# LMD18200_2_7_5.net
KiCad netlist of a schematic drawn in EAGLE
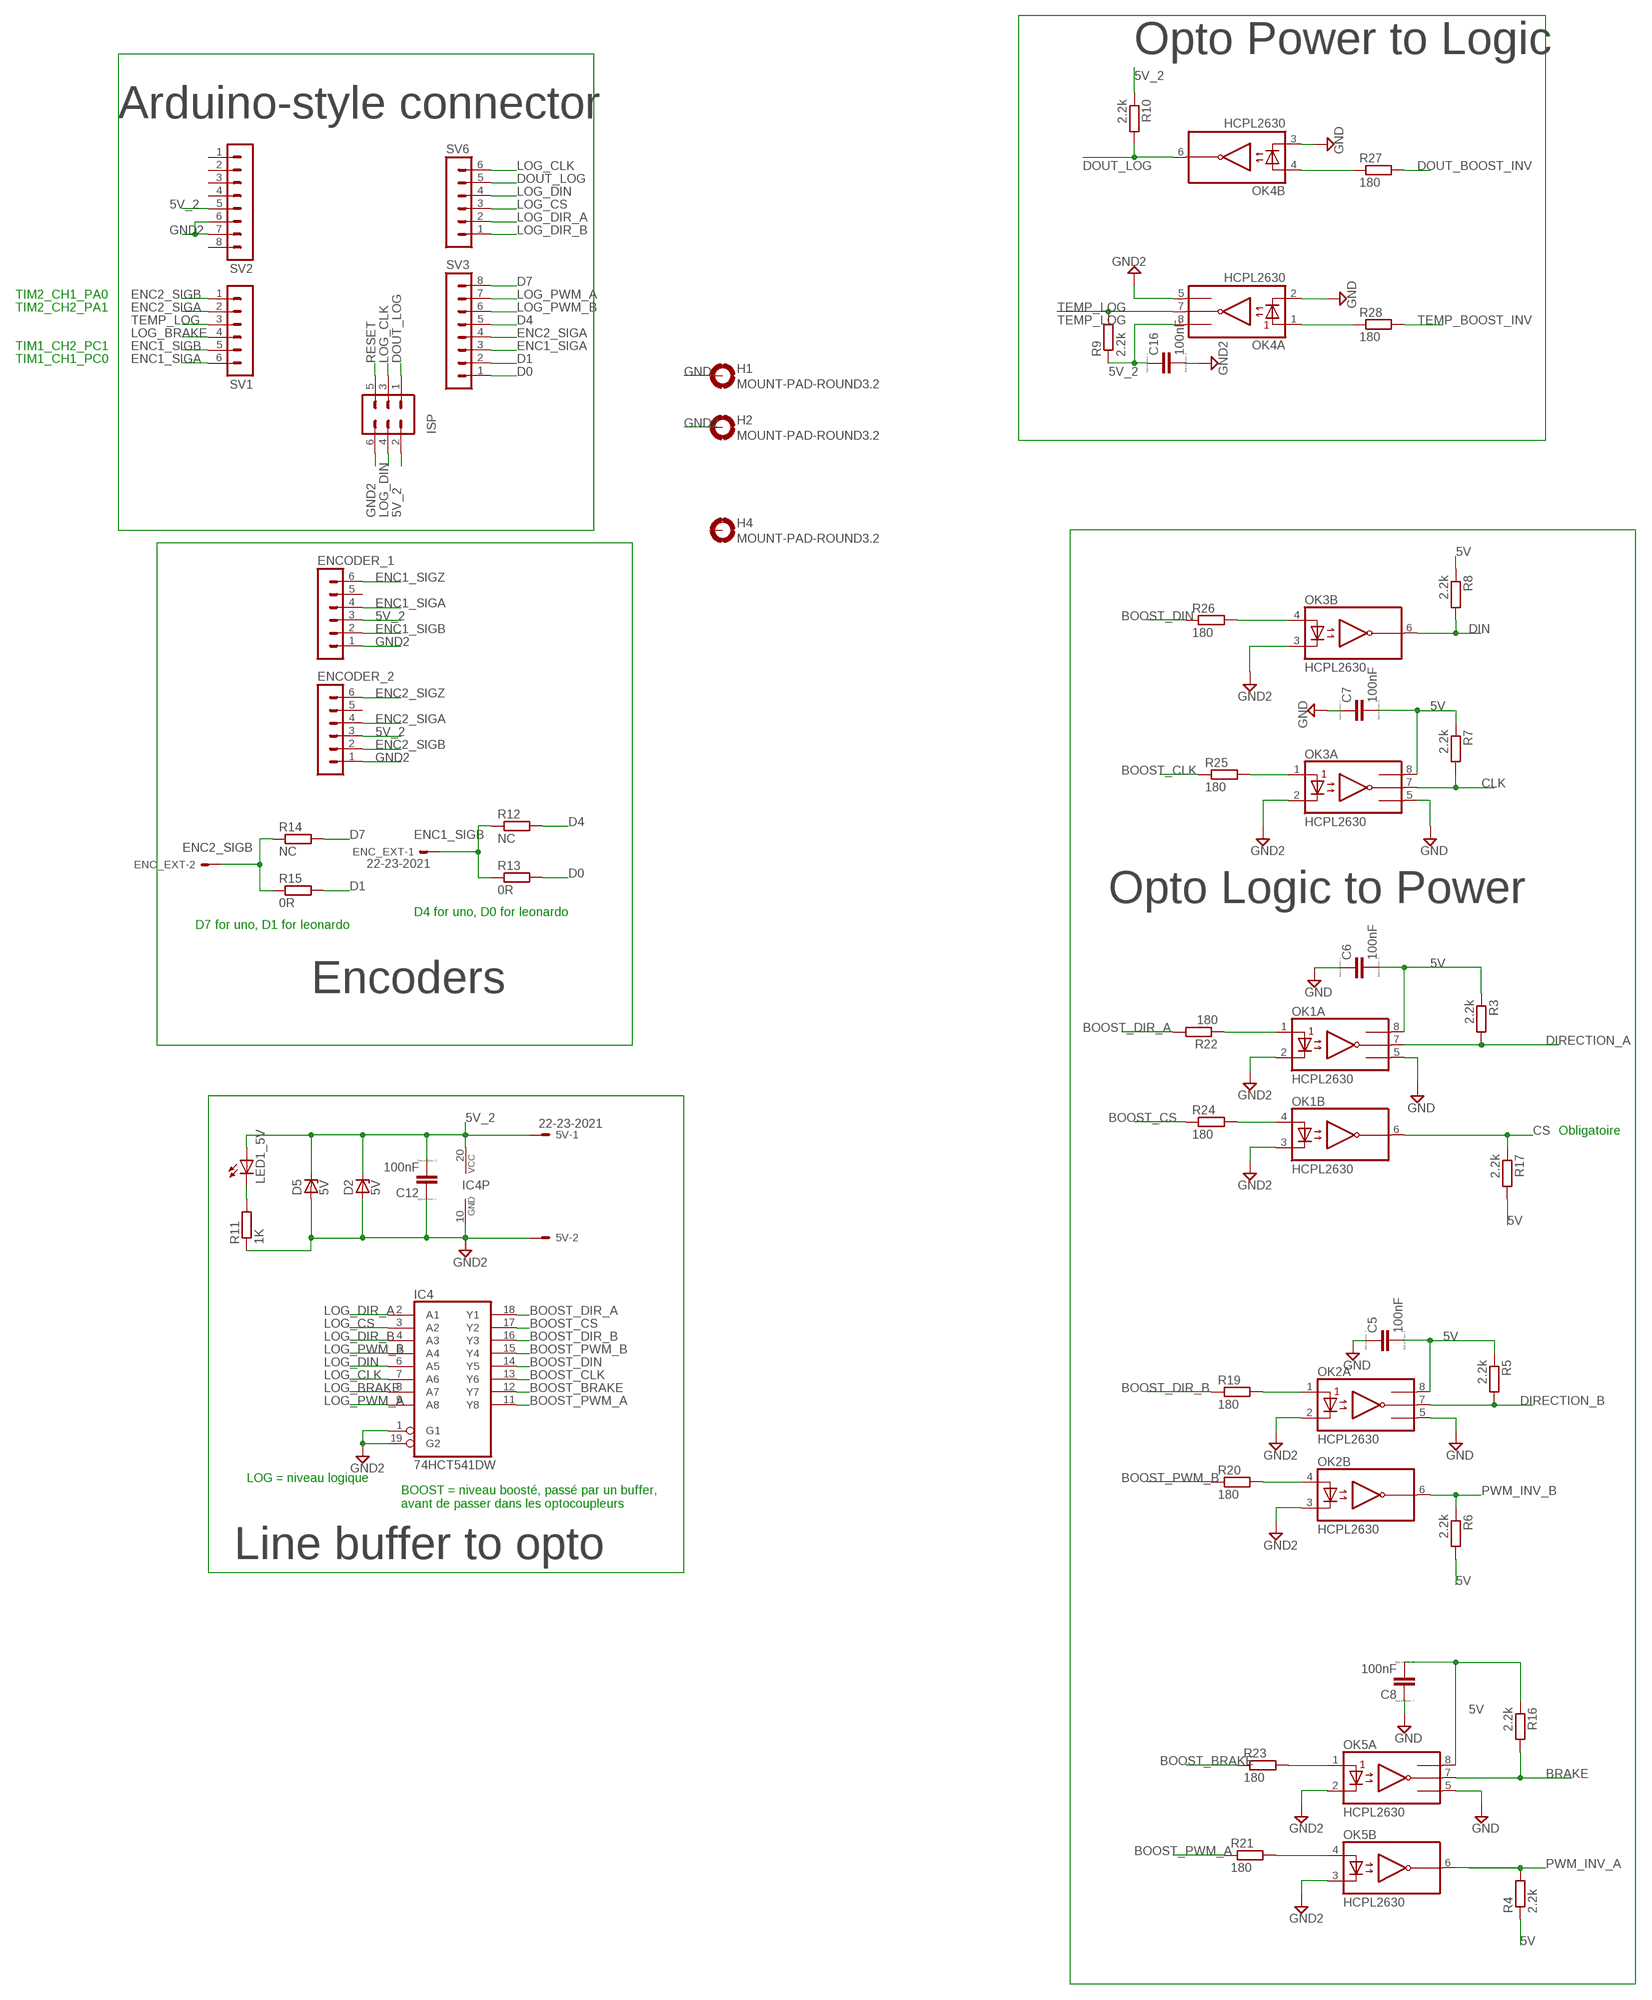
[diagram p0: schematic, sheet 1, part 1 of 2]
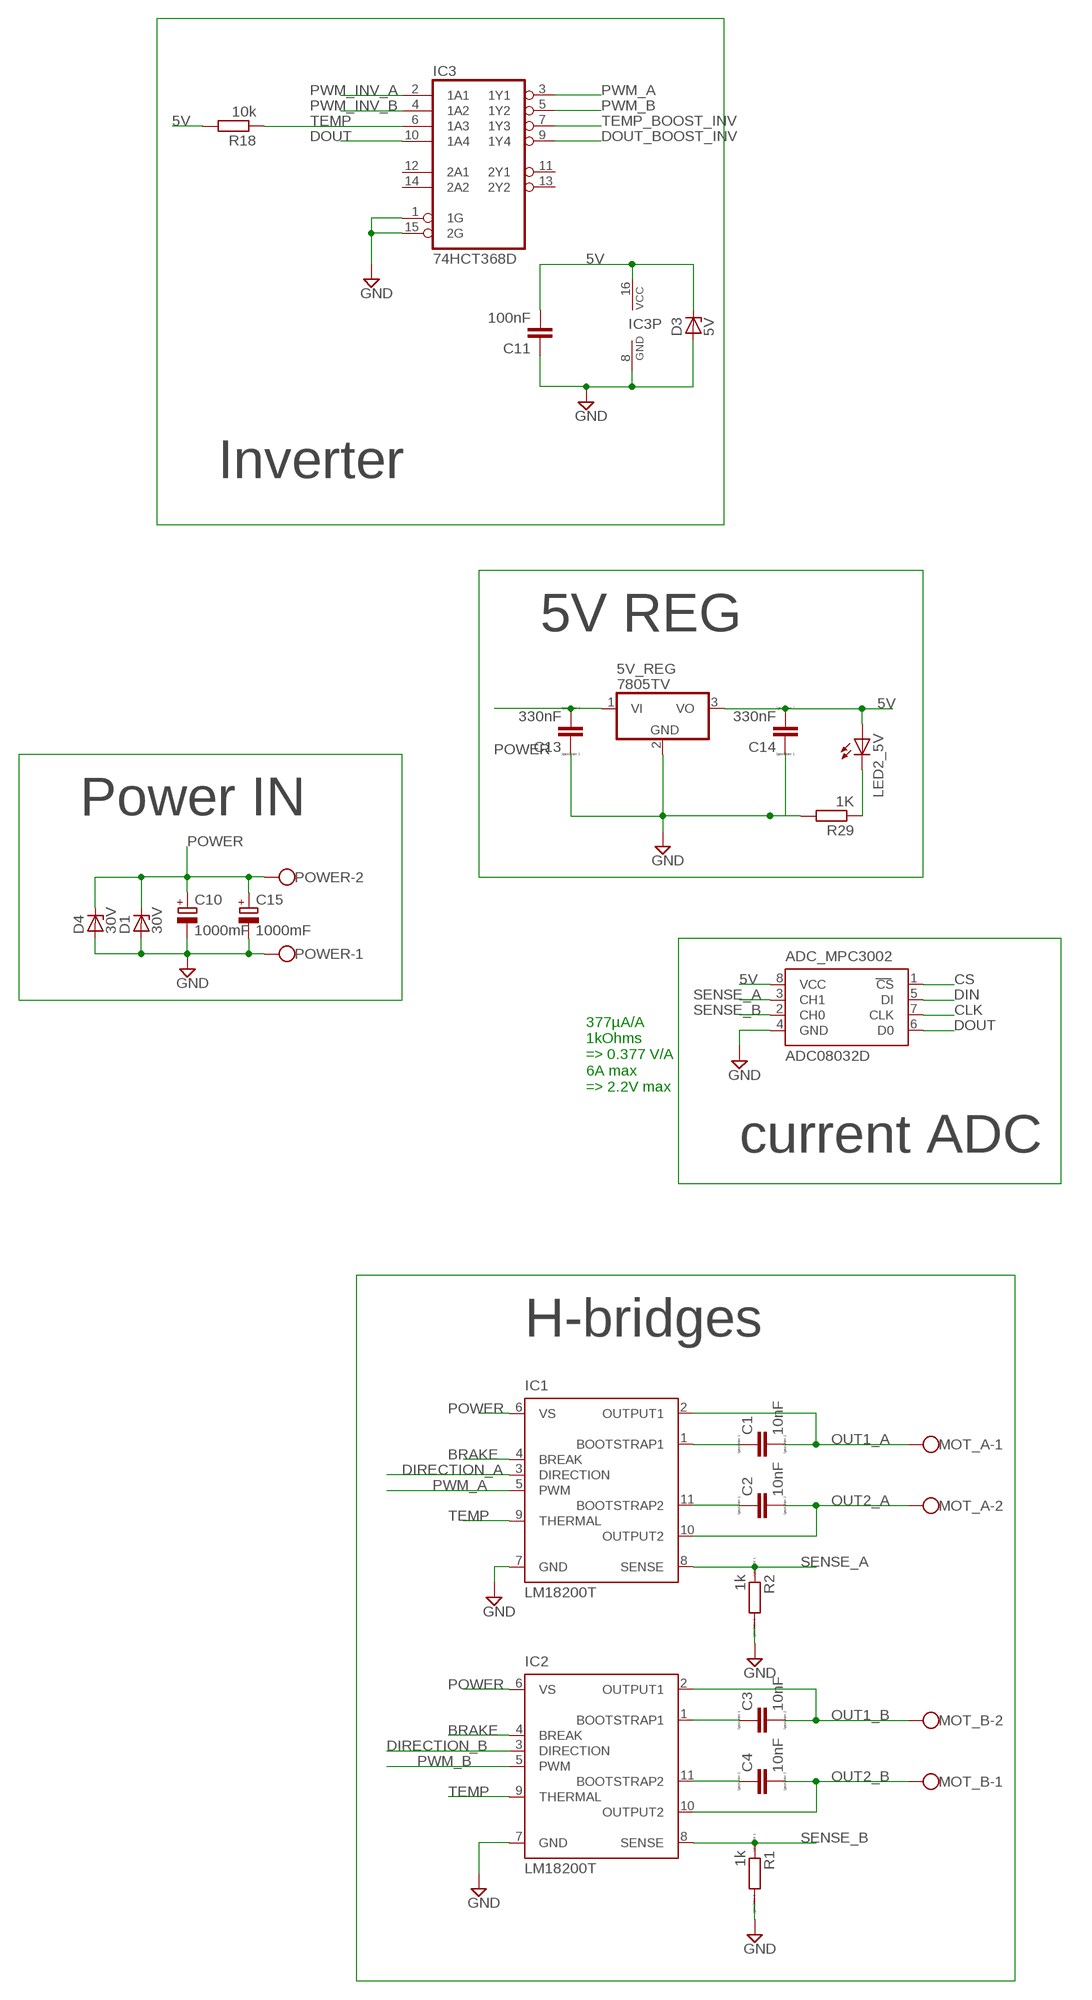
[diagram p1: schematic, sheet 1, part 2 of 2]

(export (version "E")
  (design (tool "Eeschema 10.0.6"))
  (components
    (comp (ref "5V")
      (value "22-23-2021")
      (footprint "eagle-import:22-23-2021")
      (fields (field (name "MF") "MOLEX"))
      (libsource (lib "eagle-import") (part "22-23-2021"))
    )
    (comp (ref "5V_REG")
      (value "7805TV")
      (footprint "eagle-import:TO220V")
      (libsource (lib "eagle-import") (part "78TV05"))
    )
    (comp (ref "ADC_MPC3002")
      (value "ADC08032D")
      (footprint "eagle-import:SO08")
      (libsource (lib "eagle-import") (part "ADC08032D"))
    )
    (comp (ref "C1")
      (value "10nF")
      (footprint "eagle-import:C0603")
      (libsource (lib "eagle-import") (part "CC0603"))
    )
    (comp (ref "C2")
      (value "10nF")
      (footprint "eagle-import:C0603")
      (libsource (lib "eagle-import") (part "CC0603"))
    )
    (comp (ref "C3")
      (value "10nF")
      (footprint "eagle-import:C0603")
      (libsource (lib "eagle-import") (part "CC0603"))
    )
    (comp (ref "C4")
      (value "10nF")
      (footprint "eagle-import:C0603")
      (libsource (lib "eagle-import") (part "CC0603"))
    )
    (comp (ref "C5")
      (value "100nF")
      (footprint "eagle-import:C0603")
      (libsource (lib "eagle-import") (part "CC0603"))
    )
    (comp (ref "C6")
      (value "100nF")
      (footprint "eagle-import:C0603")
      (libsource (lib "eagle-import") (part "CC0603"))
    )
    (comp (ref "C7")
      (value "100nF")
      (footprint "eagle-import:C0603")
      (libsource (lib "eagle-import") (part "CC0603"))
    )
    (comp (ref "C8")
      (value "100nF")
      (footprint "eagle-import:C0603")
      (libsource (lib "eagle-import") (part "CC0603"))
    )
    (comp (ref "C10")
      (value "1000mF")
      (footprint "eagle-import:E5-13")
      (libsource (lib "eagle-import") (part "CPOL-EUE5-13"))
    )
    (comp (ref "C11")
      (value "100nF")
      (footprint "eagle-import:C0805")
      (libsource (lib "eagle-import") (part "C-EUC0805"))
    )
    (comp (ref "C12")
      (value "100nF")
      (footprint "eagle-import:C0603")
      (libsource (lib "eagle-import") (part "CC0603"))
    )
    (comp (ref "C13")
      (value "330nF")
      (footprint "eagle-import:C0603")
      (libsource (lib "eagle-import") (part "CC0603"))
    )
    (comp (ref "C14")
      (value "330nF")
      (footprint "eagle-import:C0603")
      (libsource (lib "eagle-import") (part "CC0603"))
    )
    (comp (ref "C15")
      (value "1000mF")
      (footprint "eagle-import:E5-13")
      (libsource (lib "eagle-import") (part "CPOL-EUE5-13"))
    )
    (comp (ref "C16")
      (value "100nF")
      (footprint "eagle-import:C0603")
      (libsource (lib "eagle-import") (part "CC0603"))
    )
    (comp (ref "D1")
      (value "30V")
      (footprint "eagle-import:SOD80C")
      (libsource (lib "eagle-import") (part "ZENER-DIODESOD80C"))
    )
    (comp (ref "D2")
      (value "5V")
      (footprint "eagle-import:SOD80C")
      (libsource (lib "eagle-import") (part "ZENER-DIODESOD80C"))
    )
    (comp (ref "D3")
      (value "5V")
      (footprint "eagle-import:DO34Z7")
      (libsource (lib "eagle-import") (part "ZENER-DIODEDO34-7"))
    )
    (comp (ref "D4")
      (value "30V")
      (footprint "eagle-import:DO34Z7")
      (libsource (lib "eagle-import") (part "ZENER-DIODEDO34-7"))
    )
    (comp (ref "D5")
      (value "5V")
      (footprint "eagle-import:DO34Z7")
      (libsource (lib "eagle-import") (part "ZENER-DIODEDO34-7"))
    )
    (comp (ref "ENCODER_1")
      (value "MA06-1")
      (footprint "eagle-import:MA06-1")
      (libsource (lib "eagle-import") (part "MA06-1"))
    )
    (comp (ref "ENCODER_2")
      (value "MA06-1")
      (footprint "eagle-import:MA06-1")
      (libsource (lib "eagle-import") (part "MA06-1"))
    )
    (comp (ref "ENC_EXT")
      (value "22-23-2021")
      (footprint "eagle-import:22-23-2021")
      (fields (field (name "MF") "MOLEX"))
      (libsource (lib "eagle-import") (part "22-23-2021"))
    )
    (comp (ref "H1")
      (value "MOUNT-PAD-ROUND3.2")
      (footprint "eagle-import:3,2-PAD")
      (libsource (lib "eagle-import") (part "MOUNT-PAD-ROUND3.2"))
    )
    (comp (ref "H2")
      (value "MOUNT-PAD-ROUND3.2")
      (footprint "eagle-import:3,2-PAD")
      (libsource (lib "eagle-import") (part "MOUNT-PAD-ROUND3.2"))
    )
    (comp (ref "H4")
      (value "MOUNT-PAD-ROUND3.2")
      (footprint "eagle-import:3,2-PAD")
      (libsource (lib "eagle-import") (part "MOUNT-PAD-ROUND3.2"))
    )
    (comp (ref "IC1")
      (value "LM18200T")
      (footprint "eagle-import:TO-220-11")
      (libsource (lib "eagle-import") (part "LM18200T"))
    )
    (comp (ref "IC2")
      (value "LM18200T")
      (footprint "eagle-import:TO-220-11")
      (libsource (lib "eagle-import") (part "LM18200T"))
    )
    (comp (ref "IC3")
      (value "74HCT368D")
      (footprint "eagle-import:SO16")
      (libsource (lib "eagle-import") (part "74368DHCT"))
    )
    (comp (ref "IC4")
      (value "74HCT541DW")
      (footprint "eagle-import:SO20W")
      (libsource (lib "eagle-import") (part "74541DWHCT"))
    )
    (comp (ref "ISP")
      (value "MA03-2")
      (footprint "eagle-import:MA03-2")
      (libsource (lib "eagle-import") (part "MA03-2"))
    )
    (comp (ref "LED1_5V")
      (value "LEDSML0805")
      (footprint "eagle-import:SML0805")
      (libsource (lib "eagle-import") (part "LEDSML0805"))
    )
    (comp (ref "LED2_5V")
      (value "LEDSML0805")
      (footprint "eagle-import:SML0805")
      (libsource (lib "eagle-import") (part "LEDSML0805"))
    )
    (comp (ref "MOT_A")
      (value "W237-102")
      (footprint "eagle-import:W237-102")
      (fields (field (name "MPN") "237-102"))
      (libsource (lib "eagle-import") (part "W237-102"))
    )
    (comp (ref "MOT_B")
      (value "W237-102")
      (footprint "eagle-import:W237-102")
      (fields (field (name "MPN") "237-102"))
      (libsource (lib "eagle-import") (part "W237-102"))
    )
    (comp (ref "OK1")
      (value "HCPL2630")
      (footprint "eagle-import:DIL08")
      (fields (field (name "MF") "AGILENT TECHNOLOGIES") (field (name "MPN") "HCPL-2630-000E"))
      (libsource (lib "eagle-import") (part "HCPL2630"))
    )
    (comp (ref "OK2")
      (value "HCPL2630")
      (footprint "eagle-import:DIL08")
      (fields (field (name "MF") "AGILENT TECHNOLOGIES") (field (name "MPN") "HCPL-2630-000E"))
      (libsource (lib "eagle-import") (part "HCPL2630"))
    )
    (comp (ref "OK3")
      (value "HCPL2630")
      (footprint "eagle-import:DIL08")
      (fields (field (name "MF") "AGILENT TECHNOLOGIES") (field (name "MPN") "HCPL-2630-000E"))
      (libsource (lib "eagle-import") (part "HCPL2630"))
    )
    (comp (ref "OK4")
      (value "HCPL2630")
      (footprint "eagle-import:DIL08")
      (fields (field (name "MF") "AGILENT TECHNOLOGIES") (field (name "MPN") "HCPL-2630-000E"))
      (libsource (lib "eagle-import") (part "HCPL2630"))
    )
    (comp (ref "OK5")
      (value "HCPL2630")
      (footprint "eagle-import:DIL08")
      (fields (field (name "MF") "AGILENT TECHNOLOGIES") (field (name "MPN") "HCPL-2630-000E"))
      (libsource (lib "eagle-import") (part "HCPL2630"))
    )
    (comp (ref "POWER")
      (value "W237-102")
      (footprint "eagle-import:W237-102")
      (fields (field (name "MPN") "237-102"))
      (libsource (lib "eagle-import") (part "W237-102"))
    )
    (comp (ref "R1")
      (value "1k")
      (footprint "eagle-import:R0603")
      (libsource (lib "eagle-import") (part "RR0603"))
    )
    (comp (ref "R2")
      (value "1k")
      (footprint "eagle-import:R0603")
      (libsource (lib "eagle-import") (part "RR0603"))
    )
    (comp (ref "R3")
      (value "2.2k")
      (footprint "eagle-import:R0603")
      (libsource (lib "eagle-import") (part "R-EU_R0603"))
    )
    (comp (ref "R4")
      (value "2.2k")
      (footprint "eagle-import:R0603")
      (libsource (lib "eagle-import") (part "R-EU_R0603"))
    )
    (comp (ref "R5")
      (value "2.2k")
      (footprint "eagle-import:R0603")
      (libsource (lib "eagle-import") (part "R-EU_R0603"))
    )
    (comp (ref "R6")
      (value "2.2k")
      (footprint "eagle-import:R0603")
      (libsource (lib "eagle-import") (part "R-EU_R0603"))
    )
    (comp (ref "R7")
      (value "2.2k")
      (footprint "eagle-import:R0603")
      (libsource (lib "eagle-import") (part "R-EU_R0603"))
    )
    (comp (ref "R8")
      (value "2.2k")
      (footprint "eagle-import:R0603")
      (libsource (lib "eagle-import") (part "R-EU_R0603"))
    )
    (comp (ref "R9")
      (value "2.2k")
      (footprint "eagle-import:R0603")
      (libsource (lib "eagle-import") (part "R-EU_R0603"))
    )
    (comp (ref "R10")
      (value "2.2k")
      (footprint "eagle-import:R0603")
      (libsource (lib "eagle-import") (part "R-EU_R0603"))
    )
    (comp (ref "R11")
      (value "1K")
      (footprint "eagle-import:R0603")
      (libsource (lib "eagle-import") (part "R-EU_R0603"))
    )
    (comp (ref "R12")
      (value "NC")
      (footprint "eagle-import:R0603")
      (libsource (lib "eagle-import") (part "R-EU_R0603"))
    )
    (comp (ref "R13")
      (value "0R")
      (footprint "eagle-import:R0603")
      (libsource (lib "eagle-import") (part "R-EU_R0603"))
    )
    (comp (ref "R14")
      (value "NC")
      (footprint "eagle-import:R0603")
      (libsource (lib "eagle-import") (part "R-EU_R0603"))
    )
    (comp (ref "R15")
      (value "0R")
      (footprint "eagle-import:R0603")
      (libsource (lib "eagle-import") (part "R-EU_R0603"))
    )
    (comp (ref "R16")
      (value "2.2k")
      (footprint "eagle-import:R0603")
      (libsource (lib "eagle-import") (part "R-EU_R0603"))
    )
    (comp (ref "R17")
      (value "2.2k")
      (footprint "eagle-import:R0603")
      (libsource (lib "eagle-import") (part "R-EU_R0603"))
    )
    (comp (ref "R18")
      (value "10k")
      (footprint "eagle-import:R0603")
      (libsource (lib "eagle-import") (part "R-EU_R0603"))
    )
    (comp (ref "R19")
      (value "180")
      (footprint "eagle-import:R0603")
      (libsource (lib "eagle-import") (part "R-EU_R0603"))
    )
    (comp (ref "R20")
      (value "180")
      (footprint "eagle-import:R0603")
      (libsource (lib "eagle-import") (part "R-EU_R0603"))
    )
    (comp (ref "R21")
      (value "180")
      (footprint "eagle-import:R0603")
      (libsource (lib "eagle-import") (part "R-EU_R0603"))
    )
    (comp (ref "R22")
      (value "180")
      (footprint "eagle-import:R0603")
      (libsource (lib "eagle-import") (part "R-EU_R0603"))
    )
    (comp (ref "R23")
      (value "180")
      (footprint "eagle-import:R0603")
      (libsource (lib "eagle-import") (part "R-EU_R0603"))
    )
    (comp (ref "R24")
      (value "180")
      (footprint "eagle-import:R0603")
      (libsource (lib "eagle-import") (part "R-EU_R0603"))
    )
    (comp (ref "R25")
      (value "180")
      (footprint "eagle-import:R0603")
      (libsource (lib "eagle-import") (part "R-EU_R0603"))
    )
    (comp (ref "R26")
      (value "180")
      (footprint "eagle-import:R0603")
      (libsource (lib "eagle-import") (part "R-EU_R0603"))
    )
    (comp (ref "R27")
      (value "180")
      (footprint "eagle-import:R0603")
      (libsource (lib "eagle-import") (part "R-EU_R0603"))
    )
    (comp (ref "R28")
      (value "180")
      (footprint "eagle-import:R0603")
      (libsource (lib "eagle-import") (part "R-EU_R0603"))
    )
    (comp (ref "R29")
      (value "1K")
      (footprint "eagle-import:R0603")
      (libsource (lib "eagle-import") (part "R-EU_R0603"))
    )
    (comp (ref "SV1")
      (value "MA06-1")
      (footprint "eagle-import:MA06-1")
      (libsource (lib "eagle-import") (part "MA06-1"))
    )
    (comp (ref "SV2")
      (value "MA08-1")
      (footprint "eagle-import:MA08-1")
      (libsource (lib "eagle-import") (part "MA08-1"))
    )
    (comp (ref "SV3")
      (value "MA08-1")
      (footprint "eagle-import:MA08-1")
      (libsource (lib "eagle-import") (part "MA08-1"))
    )
    (comp (ref "SV6")
      (value "MA06-1")
      (footprint "eagle-import:MA06-1")
      (libsource (lib "eagle-import") (part "MA06-1"))
    )
  )
  (nets
    (net (code "1") (name "/5V") (class "Default")
      (node (ref "5V_REG") (pin "3") (pinfunction "VO_3") (pintype "passive"))
      (node (ref "ADC_MPC3002") (pin "8") (pinfunction "VCC_8") (pintype "power_in"))
      (node (ref "C11") (pin "2") (pinfunction "2_2") (pintype "passive"))
      (node (ref "C14") (pin "2") (pinfunction "2_2") (pintype "passive"))
      (node (ref "C5") (pin "2") (pinfunction "2_2") (pintype "passive"))
      (node (ref "C6") (pin "2") (pinfunction "2_2") (pintype "passive"))
      (node (ref "C7") (pin "2") (pinfunction "2_2") (pintype "passive"))
      (node (ref "C8") (pin "2") (pinfunction "2_2") (pintype "passive"))
      (node (ref "D3") (pin "C") (pinfunction "C_C") (pintype "passive"))
      (node (ref "IC3") (pin "16") (pinfunction "VCC_16") (pintype "power_in"))
      (node (ref "LED2_5V") (pin "A") (pinfunction "A_A") (pintype "passive"))
      (node (ref "OK1") (pin "8") (pinfunction "VCC_8") (pintype "passive"))
      (node (ref "OK2") (pin "8") (pinfunction "VCC_8") (pintype "passive"))
      (node (ref "OK3") (pin "8") (pinfunction "VCC_8") (pintype "passive"))
      (node (ref "OK5") (pin "8") (pinfunction "VCC_8") (pintype "passive"))
      (node (ref "R16") (pin "1") (pinfunction "1_1") (pintype "passive"))
      (node (ref "R17") (pin "2") (pinfunction "2_2") (pintype "passive"))
      (node (ref "R18") (pin "2") (pinfunction "2_2") (pintype "passive"))
      (node (ref "R3") (pin "1") (pinfunction "1_1") (pintype "passive"))
      (node (ref "R4") (pin "1") (pinfunction "1_1") (pintype "passive"))
      (node (ref "R5") (pin "1") (pinfunction "1_1") (pintype "passive"))
      (node (ref "R6") (pin "2") (pinfunction "2_2") (pintype "passive"))
      (node (ref "R7") (pin "1") (pinfunction "1_1") (pintype "passive"))
      (node (ref "R8") (pin "1") (pinfunction "1_1") (pintype "passive"))
    )
    (net (code "2") (name "/5V_2") (class "Default")
      (node (ref "5V") (pin "1") (pinfunction "S_1") (pintype "passive"))
      (node (ref "C12") (pin "2") (pinfunction "2_2") (pintype "passive"))
      (node (ref "C16") (pin "1") (pinfunction "1_1") (pintype "passive"))
      (node (ref "D2") (pin "C") (pinfunction "C_C") (pintype "passive"))
      (node (ref "D5") (pin "C") (pinfunction "C_C") (pintype "passive"))
      (node (ref "ENCODER_1") (pin "3") (pinfunction "3_3") (pintype "passive"))
      (node (ref "ENCODER_2") (pin "3") (pinfunction "3_3") (pintype "passive"))
      (node (ref "IC4") (pin "20") (pinfunction "VCC_20") (pintype "power_in"))
      (node (ref "ISP") (pin "2") (pinfunction "2_2") (pintype "passive"))
      (node (ref "LED1_5V") (pin "A") (pinfunction "A_A") (pintype "passive"))
      (node (ref "OK4") (pin "8") (pinfunction "VCC_8") (pintype "passive"))
      (node (ref "R10") (pin "1") (pinfunction "1_1") (pintype "passive"))
      (node (ref "R9") (pin "1") (pinfunction "1_1") (pintype "passive"))
      (node (ref "SV2") (pin "5") (pinfunction "5_5") (pintype "passive"))
    )
    (net (code "3") (name "/BOOST_BRAKE") (class "Default")
      (node (ref "IC4") (pin "12") (pinfunction "Y7_12") (pintype "tri_state"))
      (node (ref "R23") (pin "1") (pinfunction "1_1") (pintype "passive"))
    )
    (net (code "4") (name "/BOOST_CLK") (class "Default")
      (node (ref "IC4") (pin "13") (pinfunction "Y6_13") (pintype "tri_state"))
      (node (ref "R25") (pin "1") (pinfunction "1_1") (pintype "passive"))
    )
    (net (code "5") (name "/BOOST_CS") (class "Default")
      (node (ref "IC4") (pin "17") (pinfunction "Y2_17") (pintype "tri_state"))
      (node (ref "R24") (pin "1") (pinfunction "1_1") (pintype "passive"))
    )
    (net (code "6") (name "/BOOST_DIN") (class "Default")
      (node (ref "IC4") (pin "14") (pinfunction "Y5_14") (pintype "tri_state"))
      (node (ref "R26") (pin "1") (pinfunction "1_1") (pintype "passive"))
    )
    (net (code "7") (name "/BOOST_DIR_A") (class "Default")
      (node (ref "IC4") (pin "18") (pinfunction "Y1_18") (pintype "tri_state"))
      (node (ref "R22") (pin "2") (pinfunction "2_2") (pintype "passive"))
    )
    (net (code "8") (name "/BOOST_DIR_B") (class "Default")
      (node (ref "IC4") (pin "16") (pinfunction "Y3_16") (pintype "tri_state"))
      (node (ref "R19") (pin "1") (pinfunction "1_1") (pintype "passive"))
    )
    (net (code "9") (name "/BOOST_PWM_A") (class "Default")
      (node (ref "IC4") (pin "11") (pinfunction "Y8_11") (pintype "tri_state"))
      (node (ref "R21") (pin "1") (pinfunction "1_1") (pintype "passive"))
    )
    (net (code "10") (name "/BOOST_PWM_B") (class "Default")
      (node (ref "IC4") (pin "15") (pinfunction "Y4_15") (pintype "tri_state"))
      (node (ref "R20") (pin "1") (pinfunction "1_1") (pintype "passive"))
    )
    (net (code "11") (name "/BRAKE") (class "Default")
      (node (ref "IC1") (pin "4") (pinfunction "BREAK_4") (pintype "input"))
      (node (ref "IC2") (pin "4") (pinfunction "BREAK_4") (pintype "input"))
      (node (ref "OK5") (pin "7") (pinfunction "VO1_7") (pintype "passive"))
      (node (ref "R16") (pin "2") (pinfunction "2_2") (pintype "passive"))
    )
    (net (code "12") (name "/CLK") (class "Default")
      (node (ref "ADC_MPC3002") (pin "7") (pinfunction "CLK_7") (pintype "input"))
      (node (ref "OK3") (pin "7") (pinfunction "VO1_7") (pintype "passive"))
      (node (ref "R7") (pin "2") (pinfunction "2_2") (pintype "passive"))
    )
    (net (code "13") (name "/CS") (class "Default")
      (node (ref "ADC_MPC3002") (pin "1") (pinfunction "CS_1") (pintype "input"))
      (node (ref "OK1") (pin "6") (pinfunction "VO2_6") (pintype "passive"))
      (node (ref "R17") (pin "1") (pinfunction "1_1") (pintype "passive"))
    )
    (net (code "14") (name "/D0") (class "Default")
      (node (ref "R13") (pin "2") (pinfunction "2_2") (pintype "passive"))
      (node (ref "SV3") (pin "1") (pinfunction "1_1") (pintype "passive"))
    )
    (net (code "15") (name "/D1") (class "Default")
      (node (ref "R15") (pin "2") (pinfunction "2_2") (pintype "passive"))
      (node (ref "SV3") (pin "2") (pinfunction "2_2") (pintype "passive"))
    )
    (net (code "16") (name "/D4") (class "Default")
      (node (ref "R12") (pin "2") (pinfunction "2_2") (pintype "passive"))
      (node (ref "SV3") (pin "5") (pinfunction "5_5") (pintype "passive"))
    )
    (net (code "17") (name "/D7") (class "Default")
      (node (ref "R14") (pin "2") (pinfunction "2_2") (pintype "passive"))
      (node (ref "SV3") (pin "8") (pinfunction "8_8") (pintype "passive"))
    )
    (net (code "18") (name "/DIN") (class "Default")
      (node (ref "ADC_MPC3002") (pin "5") (pinfunction "DI_5") (pintype "input"))
      (node (ref "OK3") (pin "6") (pinfunction "VO2_6") (pintype "passive"))
      (node (ref "R8") (pin "2") (pinfunction "2_2") (pintype "passive"))
    )
    (net (code "19") (name "/DIRECTION_A") (class "Default")
      (node (ref "IC1") (pin "3") (pinfunction "DIRECTION_3") (pintype "input"))
      (node (ref "OK1") (pin "7") (pinfunction "VO1_7") (pintype "passive"))
      (node (ref "R3") (pin "2") (pinfunction "2_2") (pintype "passive"))
    )
    (net (code "20") (name "/DIRECTION_B") (class "Default")
      (node (ref "IC2") (pin "3") (pinfunction "DIRECTION_3") (pintype "input"))
      (node (ref "OK2") (pin "7") (pinfunction "VO1_7") (pintype "passive"))
      (node (ref "R5") (pin "2") (pinfunction "2_2") (pintype "passive"))
    )
    (net (code "21") (name "/DOUT") (class "Default")
      (node (ref "ADC_MPC3002") (pin "6") (pinfunction "D0_6") (pintype "tri_state"))
      (node (ref "IC3") (pin "10") (pinfunction "1A4_10") (pintype "input"))
    )
    (net (code "22") (name "/DOUT_BOOST_INV") (class "Default")
      (node (ref "IC3") (pin "9") (pinfunction "1Y4_9") (pintype "tri_state"))
      (node (ref "R27") (pin "2") (pinfunction "2_2") (pintype "passive"))
    )
    (net (code "23") (name "/DOUT_LOG") (class "Default")
      (node (ref "ISP") (pin "1") (pinfunction "1_1") (pintype "passive"))
      (node (ref "OK4") (pin "6") (pinfunction "VO2_6") (pintype "passive"))
      (node (ref "R10") (pin "2") (pinfunction "2_2") (pintype "passive"))
      (node (ref "SV6") (pin "5") (pinfunction "5_5") (pintype "passive"))
    )
    (net (code "24") (name "/ENC1_SIGA") (class "Default")
      (node (ref "ENCODER_1") (pin "4") (pinfunction "4_4") (pintype "passive"))
      (node (ref "SV1") (pin "6") (pinfunction "6_6") (pintype "passive"))
      (node (ref "SV3") (pin "3") (pinfunction "3_3") (pintype "passive"))
    )
    (net (code "25") (name "/ENC1_SIGB") (class "Default")
      (node (ref "ENCODER_1") (pin "2") (pinfunction "2_2") (pintype "passive"))
      (node (ref "ENC_EXT") (pin "1") (pinfunction "S_1") (pintype "passive"))
      (node (ref "R12") (pin "1") (pinfunction "1_1") (pintype "passive"))
      (node (ref "R13") (pin "1") (pinfunction "1_1") (pintype "passive"))
      (node (ref "SV1") (pin "5") (pinfunction "5_5") (pintype "passive"))
    )
    (net (code "26") (name "/ENC1_SIGZ") (class "Default")
      (node (ref "ENCODER_1") (pin "6") (pinfunction "6_6") (pintype "passive"))
    )
    (net (code "27") (name "/ENC2_SIGA") (class "Default")
      (node (ref "ENCODER_2") (pin "4") (pinfunction "4_4") (pintype "passive"))
      (node (ref "SV1") (pin "2") (pinfunction "2_2") (pintype "passive"))
      (node (ref "SV3") (pin "4") (pinfunction "4_4") (pintype "passive"))
    )
    (net (code "28") (name "/ENC2_SIGB") (class "Default")
      (node (ref "ENCODER_2") (pin "2") (pinfunction "2_2") (pintype "passive"))
      (node (ref "ENC_EXT") (pin "2") (pinfunction "S_2") (pintype "passive"))
      (node (ref "R14") (pin "1") (pinfunction "1_1") (pintype "passive"))
      (node (ref "R15") (pin "1") (pinfunction "1_1") (pintype "passive"))
      (node (ref "SV1") (pin "1") (pinfunction "1_1") (pintype "passive"))
    )
    (net (code "29") (name "/ENC2_SIGZ") (class "Default")
      (node (ref "ENCODER_2") (pin "6") (pinfunction "6_6") (pintype "passive"))
    )
    (net (code "30") (name "/LOG_BRAKE") (class "Default")
      (node (ref "IC4") (pin "8") (pinfunction "A7_8") (pintype "input"))
      (node (ref "SV1") (pin "4") (pinfunction "4_4") (pintype "passive"))
    )
    (net (code "31") (name "/LOG_CLK") (class "Default")
      (node (ref "IC4") (pin "7") (pinfunction "A6_7") (pintype "input"))
      (node (ref "ISP") (pin "3") (pinfunction "3_3") (pintype "passive"))
      (node (ref "SV6") (pin "6") (pinfunction "6_6") (pintype "passive"))
    )
    (net (code "32") (name "/LOG_CS") (class "Default")
      (node (ref "IC4") (pin "3") (pinfunction "A2_3") (pintype "input"))
      (node (ref "SV6") (pin "3") (pinfunction "3_3") (pintype "passive"))
    )
    (net (code "33") (name "/LOG_DIN") (class "Default")
      (node (ref "IC4") (pin "6") (pinfunction "A5_6") (pintype "input"))
      (node (ref "ISP") (pin "4") (pinfunction "4_4") (pintype "passive"))
      (node (ref "SV6") (pin "4") (pinfunction "4_4") (pintype "passive"))
    )
    (net (code "34") (name "/LOG_DIR_A") (class "Default")
      (node (ref "IC4") (pin "2") (pinfunction "A1_2") (pintype "input"))
      (node (ref "SV6") (pin "2") (pinfunction "2_2") (pintype "passive"))
    )
    (net (code "35") (name "/LOG_DIR_B") (class "Default")
      (node (ref "IC4") (pin "4") (pinfunction "A3_4") (pintype "input"))
      (node (ref "SV6") (pin "1") (pinfunction "1_1") (pintype "passive"))
    )
    (net (code "36") (name "/LOG_PWM_A") (class "Default")
      (node (ref "IC4") (pin "9") (pinfunction "A8_9") (pintype "input"))
      (node (ref "SV3") (pin "7") (pinfunction "7_7") (pintype "passive"))
    )
    (net (code "37") (name "/LOG_PWM_B") (class "Default")
      (node (ref "IC4") (pin "5") (pinfunction "A4_5") (pintype "input"))
      (node (ref "SV3") (pin "6") (pinfunction "6_6") (pintype "passive"))
    )
    (net (code "38") (name "/OUT1_A") (class "Default")
      (node (ref "C1") (pin "2") (pinfunction "2_2") (pintype "passive"))
      (node (ref "IC1") (pin "2") (pinfunction "OUTPUT1_2") (pintype "output"))
      (node (ref "MOT_A") (pin "1") (pinfunction "KL_1") (pintype "passive"))
    )
    (net (code "39") (name "/OUT1_B") (class "Default")
      (node (ref "C3") (pin "2") (pinfunction "2_2") (pintype "passive"))
      (node (ref "IC2") (pin "2") (pinfunction "OUTPUT1_2") (pintype "output"))
      (node (ref "MOT_B") (pin "2") (pinfunction "KL_2") (pintype "passive"))
    )
    (net (code "40") (name "/OUT2_A") (class "Default")
      (node (ref "C2") (pin "2") (pinfunction "2_2") (pintype "passive"))
      (node (ref "IC1") (pin "10") (pinfunction "OUTPUT2_10") (pintype "output"))
      (node (ref "MOT_A") (pin "2") (pinfunction "KL_2") (pintype "passive"))
    )
    (net (code "41") (name "/OUT2_B") (class "Default")
      (node (ref "C4") (pin "2") (pinfunction "2_2") (pintype "passive"))
      (node (ref "IC2") (pin "10") (pinfunction "OUTPUT2_10") (pintype "output"))
      (node (ref "MOT_B") (pin "1") (pinfunction "KL_1") (pintype "passive"))
    )
    (net (code "42") (name "/POWER") (class "Default")
      (node (ref "5V_REG") (pin "1") (pinfunction "VI_1") (pintype "input"))
      (node (ref "C10") (pin "+") (pinfunction "+_+") (pintype "passive"))
      (node (ref "C13") (pin "2") (pinfunction "2_2") (pintype "passive"))
      (node (ref "C15") (pin "+") (pinfunction "+_+") (pintype "passive"))
      (node (ref "D1") (pin "C") (pinfunction "C_C") (pintype "passive"))
      (node (ref "D4") (pin "C") (pinfunction "C_C") (pintype "passive"))
      (node (ref "IC1") (pin "6") (pinfunction "VS_6") (pintype "power_in"))
      (node (ref "IC2") (pin "6") (pinfunction "VS_6") (pintype "power_in"))
      (node (ref "POWER") (pin "2") (pinfunction "KL_2") (pintype "passive"))
    )
    (net (code "43") (name "/PWM_A") (class "Default")
      (node (ref "IC1") (pin "5") (pinfunction "PWM_5") (pintype "input"))
      (node (ref "IC3") (pin "3") (pinfunction "1Y1_3") (pintype "tri_state"))
    )
    (net (code "44") (name "/PWM_B") (class "Default")
      (node (ref "IC2") (pin "5") (pinfunction "PWM_5") (pintype "input"))
      (node (ref "IC3") (pin "5") (pinfunction "1Y2_5") (pintype "tri_state"))
    )
    (net (code "45") (name "/PWM_INV_A") (class "Default")
      (node (ref "IC3") (pin "2") (pinfunction "1A1_2") (pintype "input"))
      (node (ref "OK5") (pin "6") (pinfunction "VO2_6") (pintype "passive"))
      (node (ref "R4") (pin "2") (pinfunction "2_2") (pintype "passive"))
    )
    (net (code "46") (name "/PWM_INV_B") (class "Default")
      (node (ref "IC3") (pin "4") (pinfunction "1A2_4") (pintype "input"))
      (node (ref "OK2") (pin "6") (pinfunction "VO2_6") (pintype "passive"))
      (node (ref "R6") (pin "1") (pinfunction "1_1") (pintype "passive"))
    )
    (net (code "47") (name "/RESET") (class "Default")
      (node (ref "ISP") (pin "5") (pinfunction "5_5") (pintype "passive"))
    )
    (net (code "48") (name "/SENSE_A") (class "Default")
      (node (ref "ADC_MPC3002") (pin "3") (pinfunction "CH1_3") (pintype "input"))
      (node (ref "IC1") (pin "8") (pinfunction "SENSE_8") (pintype "output"))
      (node (ref "R2") (pin "1") (pinfunction "1_1") (pintype "passive"))
    )
    (net (code "49") (name "/SENSE_B") (class "Default")
      (node (ref "ADC_MPC3002") (pin "2") (pinfunction "CH0_2") (pintype "input"))
      (node (ref "IC2") (pin "8") (pinfunction "SENSE_8") (pintype "output"))
      (node (ref "R1") (pin "1") (pinfunction "1_1") (pintype "passive"))
    )
    (net (code "50") (name "/TEMP") (class "Default")
      (node (ref "IC1") (pin "9") (pinfunction "THERMAL_9") (pintype "output"))
      (node (ref "IC2") (pin "9") (pinfunction "THERMAL_9") (pintype "output"))
      (node (ref "IC3") (pin "6") (pinfunction "1A3_6") (pintype "input"))
      (node (ref "R18") (pin "1") (pinfunction "1_1") (pintype "passive"))
    )
    (net (code "51") (name "/TEMP_BOOST_INV") (class "Default")
      (node (ref "IC3") (pin "7") (pinfunction "1Y3_7") (pintype "tri_state"))
      (node (ref "R28") (pin "2") (pinfunction "2_2") (pintype "passive"))
    )
    (net (code "52") (name "/TEMP_LOG") (class "Default")
      (node (ref "OK4") (pin "7") (pinfunction "VO1_7") (pintype "passive"))
      (node (ref "R9") (pin "2") (pinfunction "2_2") (pintype "passive"))
      (node (ref "SV1") (pin "3") (pinfunction "3_3") (pintype "passive"))
    )
    (net (code "53") (name "GND") (class "Default")
      (node (ref "5V_REG") (pin "2") (pinfunction "GND_2") (pintype "passive"))
      (node (ref "ADC_MPC3002") (pin "4") (pinfunction "GND_4") (pintype "power_in"))
      (node (ref "C10") (pin "-") (pinfunction "-_-") (pintype "passive"))
      (node (ref "C11") (pin "1") (pinfunction "1_1") (pintype "passive"))
      (node (ref "C13") (pin "1") (pinfunction "1_1") (pintype "passive"))
      (node (ref "C14") (pin "1") (pinfunction "1_1") (pintype "passive"))
      (node (ref "C15") (pin "-") (pinfunction "-_-") (pintype "passive"))
      (node (ref "C5") (pin "1") (pinfunction "1_1") (pintype "passive"))
      (node (ref "C6") (pin "1") (pinfunction "1_1") (pintype "passive"))
      (node (ref "C7") (pin "1") (pinfunction "1_1") (pintype "passive"))
      (node (ref "C8") (pin "1") (pinfunction "1_1") (pintype "passive"))
      (node (ref "D1") (pin "A") (pinfunction "A_A") (pintype "passive"))
      (node (ref "D3") (pin "A") (pinfunction "A_A") (pintype "passive"))
      (node (ref "D4") (pin "A") (pinfunction "A_A") (pintype "passive"))
      (node (ref "H1") (pin "B3,2") (pinfunction "MOUNT_B3,2") (pintype "passive"))
      (node (ref "IC1") (pin "7") (pinfunction "GND_7") (pintype "power_in"))
      (node (ref "IC2") (pin "7") (pinfunction "GND_7") (pintype "power_in"))
      (node (ref "IC3") (pin "1") (pinfunction "1G_1") (pintype "input"))
      (node (ref "IC3") (pin "15") (pinfunction "2G_15") (pintype "input"))
      (node (ref "IC3") (pin "8") (pinfunction "GND_8") (pintype "power_in"))
      (node (ref "OK1") (pin "5") (pinfunction "GND_5") (pintype "passive"))
      (node (ref "OK2") (pin "5") (pinfunction "GND_5") (pintype "passive"))
      (node (ref "OK3") (pin "5") (pinfunction "GND_5") (pintype "passive"))
      (node (ref "OK4") (pin "2") (pinfunction "C1_2") (pintype "passive"))
      (node (ref "OK4") (pin "3") (pinfunction "C2_3") (pintype "passive"))
      (node (ref "OK5") (pin "5") (pinfunction "GND_5") (pintype "passive"))
      (node (ref "POWER") (pin "1") (pinfunction "KL_1") (pintype "passive"))
      (node (ref "R1") (pin "2") (pinfunction "2_2") (pintype "passive"))
      (node (ref "R2") (pin "2") (pinfunction "2_2") (pintype "passive"))
      (node (ref "R29") (pin "2") (pinfunction "2_2") (pintype "passive"))
    )
    (net (code "54") (name "GND2") (class "Default")
      (node (ref "5V") (pin "2") (pinfunction "S_2") (pintype "passive"))
      (node (ref "C12") (pin "1") (pinfunction "1_1") (pintype "passive"))
      (node (ref "C16") (pin "2") (pinfunction "2_2") (pintype "passive"))
      (node (ref "D2") (pin "A") (pinfunction "A_A") (pintype "passive"))
      (node (ref "D5") (pin "A") (pinfunction "A_A") (pintype "passive"))
      (node (ref "ENCODER_1") (pin "1") (pinfunction "1_1") (pintype "passive"))
      (node (ref "ENCODER_2") (pin "1") (pinfunction "1_1") (pintype "passive"))
      (node (ref "H2") (pin "B3,2") (pinfunction "MOUNT_B3,2") (pintype "passive"))
      (node (ref "IC4") (pin "1") (pinfunction "G1_1") (pintype "input"))
      (node (ref "IC4") (pin "10") (pinfunction "GND_10") (pintype "power_in"))
      (node (ref "IC4") (pin "19") (pinfunction "G2_19") (pintype "input"))
      (node (ref "ISP") (pin "6") (pinfunction "6_6") (pintype "passive"))
      (node (ref "OK1") (pin "2") (pinfunction "C1_2") (pintype "passive"))
      (node (ref "OK1") (pin "3") (pinfunction "C2_3") (pintype "passive"))
      (node (ref "OK2") (pin "2") (pinfunction "C1_2") (pintype "passive"))
      (node (ref "OK2") (pin "3") (pinfunction "C2_3") (pintype "passive"))
      (node (ref "OK3") (pin "2") (pinfunction "C1_2") (pintype "passive"))
      (node (ref "OK3") (pin "3") (pinfunction "C2_3") (pintype "passive"))
      (node (ref "OK4") (pin "5") (pinfunction "GND_5") (pintype "passive"))
      (node (ref "OK5") (pin "2") (pinfunction "C1_2") (pintype "passive"))
      (node (ref "OK5") (pin "3") (pinfunction "C2_3") (pintype "passive"))
      (node (ref "R11") (pin "1") (pinfunction "1_1") (pintype "passive"))
      (node (ref "SV2") (pin "6") (pinfunction "6_6") (pintype "passive"))
      (node (ref "SV2") (pin "7") (pinfunction "7_7") (pintype "passive"))
    )
    (net (code "55") (name "Net-(IC1-BOOTSTRAP1)") (class "Default")
      (node (ref "C1") (pin "1") (pinfunction "1_1") (pintype "passive"))
      (node (ref "IC1") (pin "1") (pinfunction "BOOTSTRAP1_1") (pintype "input"))
    )
    (net (code "56") (name "Net-(IC1-BOOTSTRAP2)") (class "Default")
      (node (ref "C2") (pin "1") (pinfunction "1_1") (pintype "passive"))
      (node (ref "IC1") (pin "11") (pinfunction "BOOTSTRAP2_11") (pintype "input"))
    )
    (net (code "57") (name "Net-(IC2-BOOTSTRAP1)") (class "Default")
      (node (ref "C3") (pin "1") (pinfunction "1_1") (pintype "passive"))
      (node (ref "IC2") (pin "1") (pinfunction "BOOTSTRAP1_1") (pintype "input"))
    )
    (net (code "58") (name "Net-(IC2-BOOTSTRAP2)") (class "Default")
      (node (ref "C4") (pin "1") (pinfunction "1_1") (pintype "passive"))
      (node (ref "IC2") (pin "11") (pinfunction "BOOTSTRAP2_11") (pintype "input"))
    )
    (net (code "59") (name "Net-(LED1_5V-PadC)") (class "Default")
      (node (ref "LED1_5V") (pin "C") (pinfunction "C_C") (pintype "passive"))
      (node (ref "R11") (pin "2") (pinfunction "2_2") (pintype "passive"))
    )
    (net (code "60") (name "Net-(LED2_5V-PadC)") (class "Default")
      (node (ref "LED2_5V") (pin "C") (pinfunction "C_C") (pintype "passive"))
      (node (ref "R29") (pin "1") (pinfunction "1_1") (pintype "passive"))
    )
    (net (code "61") (name "Net-(OK1A-A1)") (class "Default")
      (node (ref "OK1") (pin "1") (pinfunction "A1_1") (pintype "passive"))
      (node (ref "R22") (pin "1") (pinfunction "1_1") (pintype "passive"))
    )
    (net (code "62") (name "Net-(OK1B-A2)") (class "Default")
      (node (ref "OK1") (pin "4") (pinfunction "A2_4") (pintype "passive"))
      (node (ref "R24") (pin "2") (pinfunction "2_2") (pintype "passive"))
    )
    (net (code "63") (name "Net-(OK2A-A1)") (class "Default")
      (node (ref "OK2") (pin "1") (pinfunction "A1_1") (pintype "passive"))
      (node (ref "R19") (pin "2") (pinfunction "2_2") (pintype "passive"))
    )
    (net (code "64") (name "Net-(OK2B-A2)") (class "Default")
      (node (ref "OK2") (pin "4") (pinfunction "A2_4") (pintype "passive"))
      (node (ref "R20") (pin "2") (pinfunction "2_2") (pintype "passive"))
    )
    (net (code "65") (name "Net-(OK3A-A1)") (class "Default")
      (node (ref "OK3") (pin "1") (pinfunction "A1_1") (pintype "passive"))
      (node (ref "R25") (pin "2") (pinfunction "2_2") (pintype "passive"))
    )
    (net (code "66") (name "Net-(OK3B-A2)") (class "Default")
      (node (ref "OK3") (pin "4") (pinfunction "A2_4") (pintype "passive"))
      (node (ref "R26") (pin "2") (pinfunction "2_2") (pintype "passive"))
    )
    (net (code "67") (name "Net-(OK4A-A1)") (class "Default")
      (node (ref "OK4") (pin "1") (pinfunction "A1_1") (pintype "passive"))
      (node (ref "R28") (pin "1") (pinfunction "1_1") (pintype "passive"))
    )
    (net (code "68") (name "Net-(OK4B-A2)") (class "Default")
      (node (ref "OK4") (pin "4") (pinfunction "A2_4") (pintype "passive"))
      (node (ref "R27") (pin "1") (pinfunction "1_1") (pintype "passive"))
    )
    (net (code "69") (name "Net-(OK5A-A1)") (class "Default")
      (node (ref "OK5") (pin "1") (pinfunction "A1_1") (pintype "passive"))
      (node (ref "R23") (pin "2") (pinfunction "2_2") (pintype "passive"))
    )
    (net (code "70") (name "Net-(OK5B-A2)") (class "Default")
      (node (ref "OK5") (pin "4") (pinfunction "A2_4") (pintype "passive"))
      (node (ref "R21") (pin "2") (pinfunction "2_2") (pintype "passive"))
    )
    (net (code "71") (name "unconnected-(ENCODER_1-Pad5)") (class "Default")
      (node (ref "ENCODER_1") (pin "5") (pinfunction "5_5") (pintype "passive"))
    )
    (net (code "72") (name "unconnected-(ENCODER_2-Pad5)") (class "Default")
      (node (ref "ENCODER_2") (pin "5") (pinfunction "5_5") (pintype "passive"))
    )
    (net (code "73") (name "unconnected-(H4-MOUNT-PadB3,2)") (class "Default")
      (node (ref "H4") (pin "B3,2") (pinfunction "MOUNT_B3,2") (pintype "passive"))
    )
    (net (code "74") (name "unconnected-(IC3A-2A1-Pad12)") (class "Default")
      (node (ref "IC3") (pin "12") (pinfunction "2A1_12") (pintype "input"))
    )
    (net (code "75") (name "unconnected-(IC3A-2A2-Pad14)") (class "Default")
      (node (ref "IC3") (pin "14") (pinfunction "2A2_14") (pintype "input"))
    )
    (net (code "76") (name "unconnected-(IC3A-2Y1-Pad11)") (class "Default")
      (node (ref "IC3") (pin "11") (pinfunction "2Y1_11") (pintype "tri_state"))
    )
    (net (code "77") (name "unconnected-(IC3A-2Y2-Pad13)") (class "Default")
      (node (ref "IC3") (pin "13") (pinfunction "2Y2_13") (pintype "tri_state"))
    )
    (net (code "78") (name "unconnected-(SV2-Pad1)") (class "Default")
      (node (ref "SV2") (pin "1") (pinfunction "1_1") (pintype "passive"))
    )
    (net (code "79") (name "unconnected-(SV2-Pad2)") (class "Default")
      (node (ref "SV2") (pin "2") (pinfunction "2_2") (pintype "passive"))
    )
    (net (code "80") (name "unconnected-(SV2-Pad3)") (class "Default")
      (node (ref "SV2") (pin "3") (pinfunction "3_3") (pintype "passive"))
    )
    (net (code "81") (name "unconnected-(SV2-Pad4)") (class "Default")
      (node (ref "SV2") (pin "4") (pinfunction "4_4") (pintype "passive"))
    )
    (net (code "82") (name "unconnected-(SV2-Pad8)") (class "Default")
      (node (ref "SV2") (pin "8") (pinfunction "8_8") (pintype "passive"))
    )
  )
)
